# Esp01Shunt.net
KiCad netlist of a schematic drawn in EAGLE
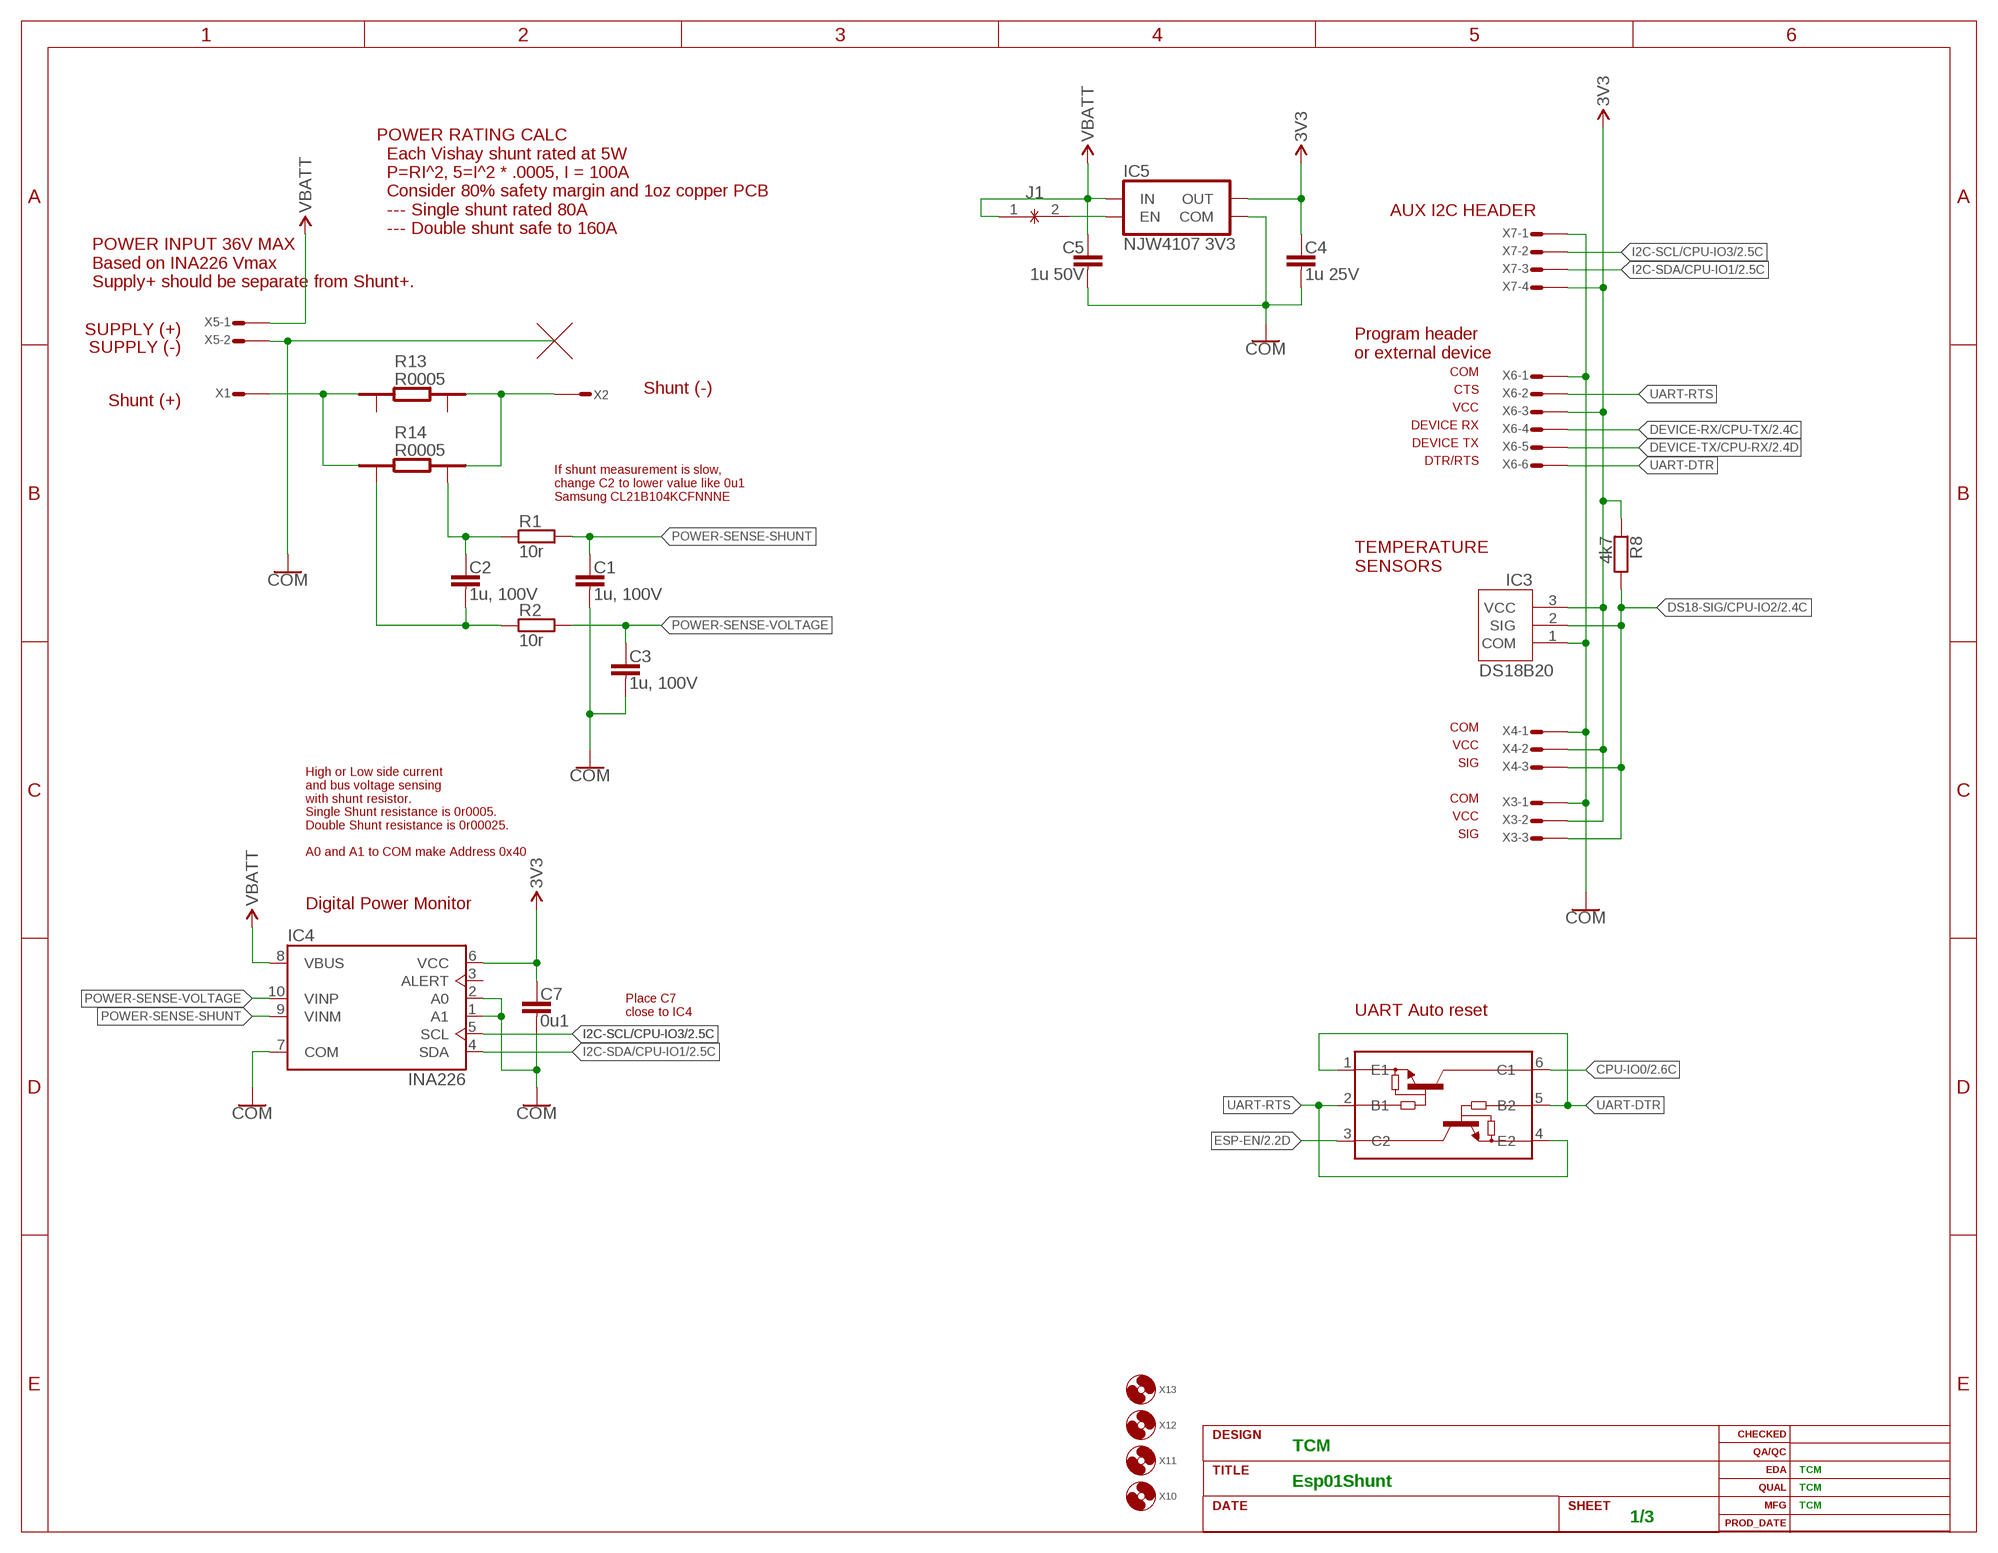
[diagram p0: schematic, sheet 1]
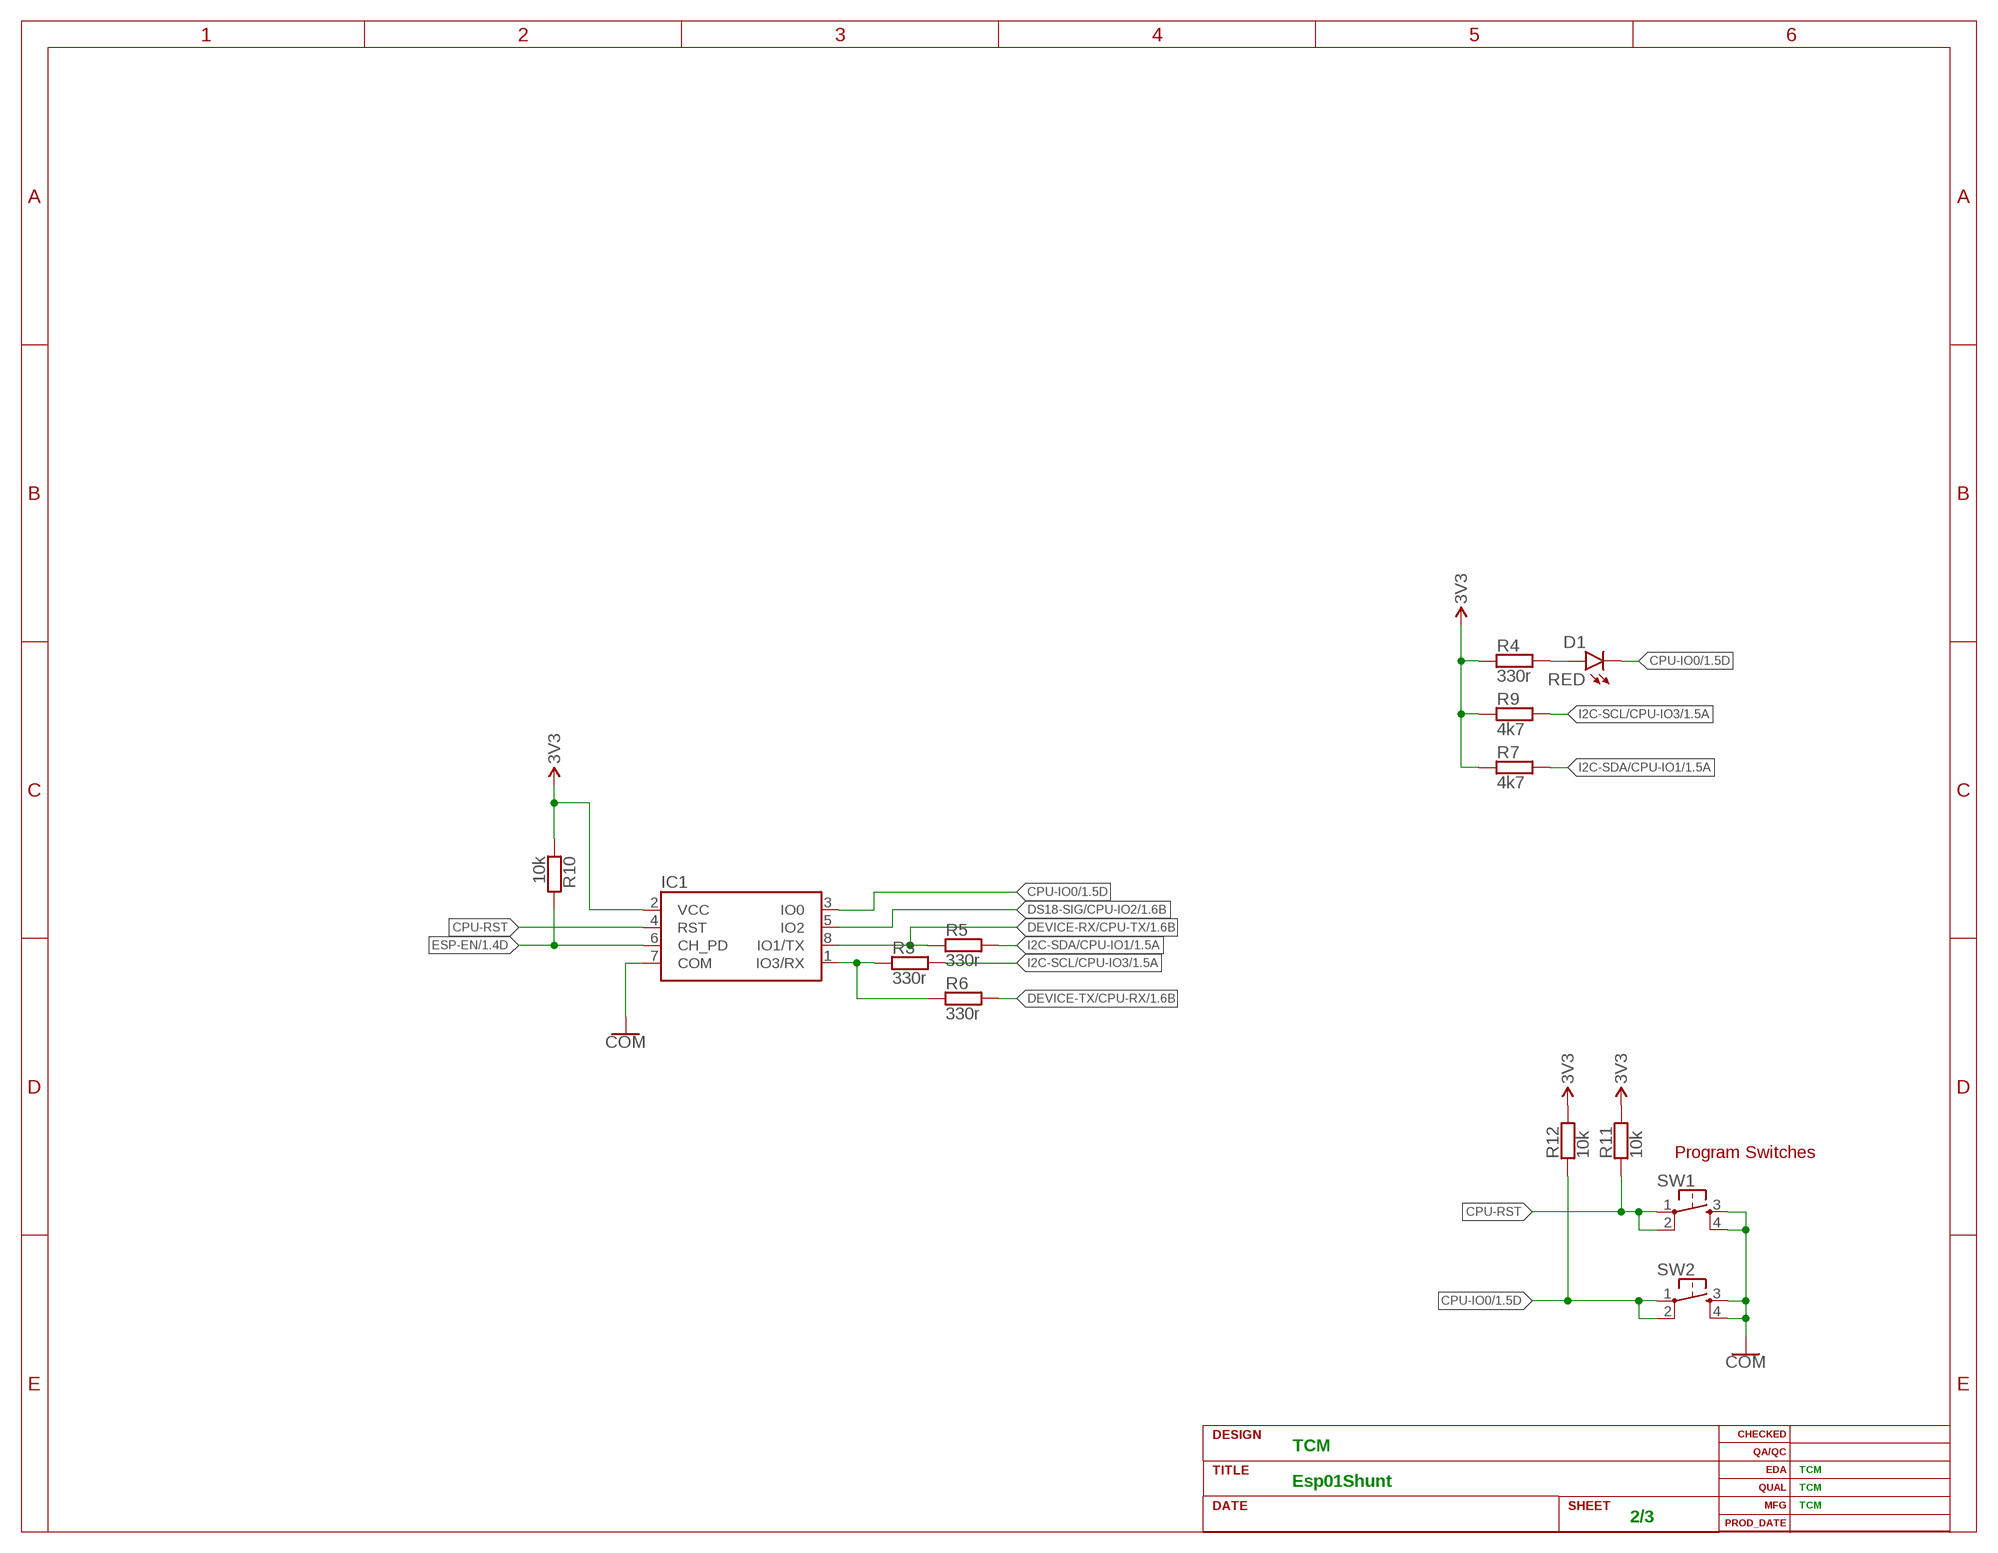
[diagram p1: schematic, sheet 2]
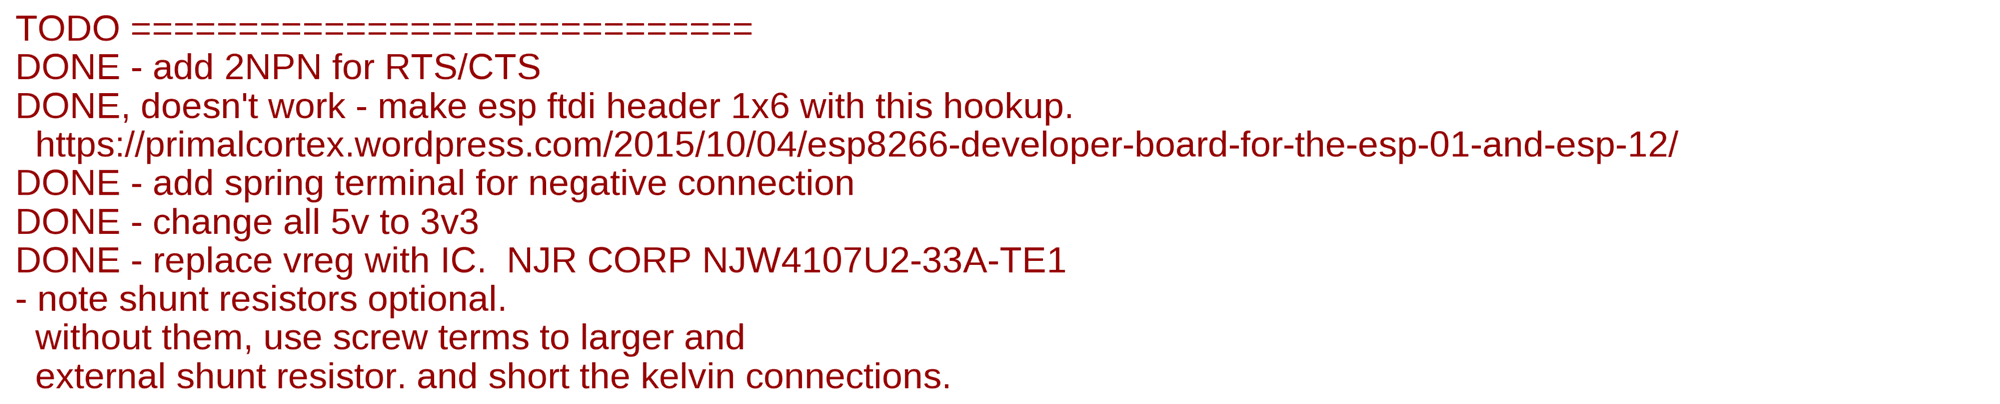
[diagram p2: schematic, sheet 3]

(export (version "E")
  (design (tool "Eeschema 10.0.6"))
  (components
    (comp (ref "D1")
      (value "RED")
      (footprint "eagle-import:LED-0805")
      (fields (field (name "MFG") "OSRAM"))
      (libsource (lib "eagle-import") (part "LED-0805-RED"))
    )
    (comp (ref "IC1")
      (value "ESP8266-01")
      (footprint "eagle-import:ESP8266-01")
      (fields (field (name "MFG") "ESPRESSIF"))
      (libsource (lib "eagle-import") (part "ESP8266-01"))
    )
    (comp (ref "R3")
      (value "330r")
      (footprint "eagle-import:R0603")
      (fields (field (name "MFG_PN") "ERJ-3EKF3300V"))
      (libsource (lib "eagle-import") (part "R-0603"))
    )
    (comp (ref "R4")
      (value "330r")
      (footprint "eagle-import:R0603")
      (fields (field (name "MFG_PN") "ERJ-3EKF3300V"))
      (libsource (lib "eagle-import") (part "R-0603"))
    )
    (comp (ref "R5")
      (value "330r")
      (footprint "eagle-import:R0603")
      (fields (field (name "MFG_PN") "ERJ-3EKF3300V"))
      (libsource (lib "eagle-import") (part "R-0603"))
    )
    (comp (ref "R6")
      (value "330r")
      (footprint "eagle-import:R0603")
      (fields (field (name "MFG_PN") "ERJ-3EKF3300V"))
      (libsource (lib "eagle-import") (part "R-0603"))
    )
    (comp (ref "R7")
      (value "4k7")
      (footprint "eagle-import:R0603")
      (fields (field (name "MFG_PN") "ERJ-3GEYJ472V"))
      (libsource (lib "eagle-import") (part "R-0603"))
    )
    (comp (ref "R9")
      (value "4k7")
      (footprint "eagle-import:R0603")
      (fields (field (name "MFG_PN") "ERJ-3GEYJ472V"))
      (libsource (lib "eagle-import") (part "R-0603"))
    )
    (comp (ref "R10")
      (value "10k")
      (footprint "eagle-import:R0603")
      (fields (field (name "MFG_PN") "ERJ-3GEYJ103V"))
      (libsource (lib "eagle-import") (part "R-0603"))
    )
    (comp (ref "R11")
      (value "10k")
      (footprint "eagle-import:R0603")
      (fields (field (name "MFG_PN") "ERJ-3GEYJ103V"))
      (libsource (lib "eagle-import") (part "R-0603"))
    )
    (comp (ref "R12")
      (value "10k")
      (footprint "eagle-import:R0603")
      (fields (field (name "MFG_PN") "ERJ-3GEYJ103V"))
      (libsource (lib "eagle-import") (part "R-0603"))
    )
    (comp (ref "SW1")
      (value "SWITCH-TACTILE-DOUBLE-SMD")
      (footprint "eagle-import:SWITCH-TACTILE-6MM-SMD")
      (fields (field (name "MFG") "C&K"))
      (libsource (lib "eagle-import") (part "SWITCH-TACTILE-DOUBLE-SMD"))
    )
    (comp (ref "SW2")
      (value "SWITCH-TACTILE-DOUBLE-SMD")
      (footprint "eagle-import:SWITCH-TACTILE-6MM-SMD")
      (fields (field (name "MFG") "C&K"))
      (libsource (lib "eagle-import") (part "SWITCH-TACTILE-DOUBLE-SMD"))
    )
    (comp (ref "C1")
      (value "1u, 100V")
      (footprint "eagle-import:1206")
      (fields (field (name "MFG") "SAMSUNG") (field (name "MFG_PN") "CL31B105KCHNNNE"))
      (libsource (lib "eagle-import") (part "C-1206"))
    )
    (comp (ref "C2")
      (value "1u, 100V")
      (footprint "eagle-import:1206")
      (fields (field (name "MFG") "SAMSUNG") (field (name "MFG_PN") "CL31B105KCHNNNE"))
      (libsource (lib "eagle-import") (part "C-1206"))
    )
    (comp (ref "C3")
      (value "1u, 100V")
      (footprint "eagle-import:1206")
      (fields (field (name "MFG") "SAMSUNG") (field (name "MFG_PN") "CL31B105KCHNNNE"))
      (libsource (lib "eagle-import") (part "C-1206"))
    )
    (comp (ref "C4")
      (value "1u 25V")
      (footprint "eagle-import:C0603")
      (fields (field (name "MFG_PN") "C1608X7R1E105K080AE"))
      (libsource (lib "eagle-import") (part "C-0603"))
    )
    (comp (ref "C5")
      (value "1u 50V")
      (footprint "eagle-import:C0603")
      (fields (field (name "MFG_PN") "C1608X5R1H105K080AB"))
      (libsource (lib "eagle-import") (part "C-0603"))
    )
    (comp (ref "C7")
      (value "0u1")
      (footprint "eagle-import:C0603")
      (fields (field (name "MFG_PN") "VJ0603Y104JXXAC"))
      (libsource (lib "eagle-import") (part "C-0603"))
    )
    (comp (ref "IC2")
      (value "MUN5214DW1T1G")
      (footprint "eagle-import:TSSOP6")
      (fields (field (name "MFG") "ONSEMI") (field (name "MFG_PN") "MUN5214DW1T1G"))
      (libsource (lib "eagle-import") (part "MUN5214-TSSOP6DW1T1G"))
    )
    (comp (ref "IC3")
      (value "DS18B20")
      (footprint "eagle-import:TO92-INLINE")
      (libsource (lib "eagle-import") (part "DS18B20-TO92-INLINE"))
    )
    (comp (ref "IC4")
      (value "INA226")
      (footprint "eagle-import:VSSOP10")
      (fields (field (name "MFG") "TEXAS"))
      (libsource (lib "eagle-import") (part "INA226-VSSOP10"))
    )
    (comp (ref "IC5")
      (value "NJW4107 3V3")
      (footprint "eagle-import:SOT89-5")
      (fields (field (name "MFG") "NJR CORP"))
      (libsource (lib "eagle-import") (part "VREG-WITH-EN-NJW4107-SOT89-5-3V3"))
    )
    (comp (ref "J1")
      (value "JUMPER-60X20-NC")
      (footprint "eagle-import:JUMPER-60X20")
      (libsource (lib "eagle-import") (part "JUMPER-60X20-NC"))
    )
    (comp (ref "R1")
      (value "10r")
      (footprint "eagle-import:R0805")
      (libsource (lib "eagle-import") (part "R-0805"))
    )
    (comp (ref "R2")
      (value "10r")
      (footprint "eagle-import:R0805")
      (libsource (lib "eagle-import") (part "R-0805"))
    )
    (comp (ref "R8")
      (value "4k7")
      (footprint "eagle-import:R0603")
      (fields (field (name "MFG_PN") "ERJ-3GEYJ472V"))
      (libsource (lib "eagle-import") (part "R-0603"))
    )
    (comp (ref "R13")
      (value "R0005")
      (footprint "eagle-import:RES-SHUNT-WSK1216")
      (fields (field (name "MFG") "VISHAY"))
      (libsource (lib "eagle-import") (part "R-SHUNT-4TERM-WSK1216-R0005"))
    )
    (comp (ref "R14")
      (value "R0005")
      (footprint "eagle-import:RES-SHUNT-WSK1216")
      (fields (field (name "MFG") "VISHAY"))
      (libsource (lib "eagle-import") (part "R-SHUNT-4TERM-WSK1216-R0005"))
    )
    (comp (ref "X1")
      (value "CON-SCREW-V-30AMP")
      (footprint "eagle-import:CON-SCREW-V-30AMP")
      (fields (field (name "MFG") "KEYSTONE"))
      (libsource (lib "eagle-import") (part "CON-SCREW-V-30AMP"))
    )
    (comp (ref "X2")
      (value "CON-SCREW-V-30AMP")
      (footprint "eagle-import:CON-SCREW-V-30AMP")
      (fields (field (name "MFG") "KEYSTONE"))
      (libsource (lib "eagle-import") (part "CON-SCREW-V-30AMP"))
    )
    (comp (ref "X3")
      (value "CON-1X3")
      (footprint "eagle-import:CON-1X3")
      (libsource (lib "eagle-import") (part "CON-1X3"))
    )
    (comp (ref "X4")
      (value "CON-1X3")
      (footprint "eagle-import:CON-1X3")
      (libsource (lib "eagle-import") (part "CON-1X3"))
    )
    (comp (ref "X5")
      (value "CON-1X2-TERM-SPRING-5MM-2834082-1")
      (footprint "eagle-import:CON-1X2-TERM-SPRING-5MM-2834082-1")
      (fields (field (name "MFG") "TE CONN"))
      (libsource (lib "eagle-import") (part "CON-1X2-TERM-SPRING-5MM-2834082-1"))
    )
    (comp (ref "X6")
      (value "CON-1X6-UART-DCE")
      (footprint "eagle-import:CON-1X6-UART-DCE")
      (libsource (lib "eagle-import") (part "CON-1X6-UART-DCE"))
    )
    (comp (ref "X7")
      (value "CON-1X4")
      (footprint "eagle-import:CON-1X4")
      (libsource (lib "eagle-import") (part "CON-1X4"))
    )
    (comp (ref "X10")
      (value "HOLE-NO-PAD-NO-SILK")
      (footprint "eagle-import:M3-NO-PAD-NO-SILK")
      (libsource (lib "eagle-import") (part "HOLE-NO-PAD-NO-SILK"))
    )
    (comp (ref "X11")
      (value "HOLE-NO-PAD-NO-SILK")
      (footprint "eagle-import:M3-NO-PAD-NO-SILK")
      (libsource (lib "eagle-import") (part "HOLE-NO-PAD-NO-SILK"))
    )
    (comp (ref "X12")
      (value "HOLE-NO-PAD-NO-SILK")
      (footprint "eagle-import:M3-NO-PAD-NO-SILK")
      (libsource (lib "eagle-import") (part "HOLE-NO-PAD-NO-SILK"))
    )
    (comp (ref "X13")
      (value "HOLE-NO-PAD-NO-SILK")
      (footprint "eagle-import:M3-NO-PAD-NO-SILK")
      (libsource (lib "eagle-import") (part "HOLE-NO-PAD-NO-SILK"))
    )
  )
  (nets
    (net (code "1") (name "3V3") (class "Default")
      (node (ref "C4") (pin "1") (pinfunction "1_1") (pintype "passive"))
      (node (ref "C7") (pin "1") (pinfunction "1_1") (pintype "passive"))
      (node (ref "IC1") (pin "2") (pinfunction "VCC_2") (pintype "power_in"))
      (node (ref "IC3") (pin "3") (pinfunction "VCC_3") (pintype "power_in"))
      (node (ref "IC4") (pin "6") (pinfunction "VCC_6") (pintype "power_in"))
      (node (ref "IC5") (pin "4") (pinfunction "OUT_4") (pintype "power_in"))
      (node (ref "R10") (pin "1") (pinfunction "1_1") (pintype "passive"))
      (node (ref "R11") (pin "2") (pinfunction "2_2") (pintype "passive"))
      (node (ref "R12") (pin "2") (pinfunction "2_2") (pintype "passive"))
      (node (ref "R4") (pin "1") (pinfunction "1_1") (pintype "passive"))
      (node (ref "R7") (pin "1") (pinfunction "1_1") (pintype "passive"))
      (node (ref "R8") (pin "1") (pinfunction "1_1") (pintype "passive"))
      (node (ref "R9") (pin "1") (pinfunction "1_1") (pintype "passive"))
      (node (ref "X3") (pin "2") (pinfunction "S_2") (pintype "passive"))
      (node (ref "X4") (pin "2") (pinfunction "S_2") (pintype "passive"))
      (node (ref "X6") (pin "3") (pinfunction "S_3") (pintype "passive"))
      (node (ref "X7") (pin "4") (pinfunction "S_4") (pintype "passive"))
    )
    (net (code "2") (name "COM") (class "Default")
      (node (ref "C1") (pin "2") (pinfunction "2_2") (pintype "passive"))
      (node (ref "C3") (pin "2") (pinfunction "2_2") (pintype "passive"))
      (node (ref "C4") (pin "2") (pinfunction "2_2") (pintype "passive"))
      (node (ref "C5") (pin "2") (pinfunction "2_2") (pintype "passive"))
      (node (ref "C7") (pin "2") (pinfunction "2_2") (pintype "passive"))
      (node (ref "IC1") (pin "7") (pinfunction "COM_7") (pintype "power_in"))
      (node (ref "IC3") (pin "1") (pinfunction "COM_1") (pintype "power_in"))
      (node (ref "IC4") (pin "1") (pinfunction "A1_1") (pintype "input"))
      (node (ref "IC4") (pin "2") (pinfunction "A0_2") (pintype "input"))
      (node (ref "IC4") (pin "7") (pinfunction "COM_7") (pintype "power_in"))
      (node (ref "IC5") (pin "2") (pinfunction "COM_2") (pintype "power_in"))
      (node (ref "IC5") (pin "5") (pinfunction "COM_5") (pintype "power_in"))
      (node (ref "SW1") (pin "3") (pinfunction "3_3") (pintype "passive"))
      (node (ref "SW1") (pin "4") (pinfunction "4_4") (pintype "passive"))
      (node (ref "SW2") (pin "3") (pinfunction "3_3") (pintype "passive"))
      (node (ref "SW2") (pin "4") (pinfunction "4_4") (pintype "passive"))
      (node (ref "X3") (pin "1") (pinfunction "S_1") (pintype "passive"))
      (node (ref "X4") (pin "1") (pinfunction "S_1") (pintype "passive"))
      (node (ref "X5") (pin "3") (pinfunction "S_3") (pintype "passive"))
      (node (ref "X5") (pin "4") (pinfunction "S_4") (pintype "passive"))
      (node (ref "X6") (pin "1") (pinfunction "S_1") (pintype "passive"))
      (node (ref "X7") (pin "1") (pinfunction "S_1") (pintype "passive"))
    )
    (net (code "3") (name "CPU-IO0") (class "Default")
      (node (ref "D1") (pin "-") (pinfunction "C_-") (pintype "passive"))
      (node (ref "IC1") (pin "3") (pinfunction "IO0_3") (pintype "bidirectional"))
      (node (ref "IC2") (pin "6") (pinfunction "C1_6") (pintype "bidirectional"))
      (node (ref "R12") (pin "1") (pinfunction "1_1") (pintype "passive"))
      (node (ref "SW2") (pin "1") (pinfunction "1_1") (pintype "passive"))
      (node (ref "SW2") (pin "2") (pinfunction "2_2") (pintype "passive"))
    )
    (net (code "4") (name "CPU-RST") (class "Default")
      (node (ref "IC1") (pin "4") (pinfunction "RST_4") (pintype "input"))
      (node (ref "R11") (pin "1") (pinfunction "1_1") (pintype "passive"))
      (node (ref "SW1") (pin "1") (pinfunction "1_1") (pintype "passive"))
      (node (ref "SW1") (pin "2") (pinfunction "2_2") (pintype "passive"))
    )
    (net (code "5") (name "DEVICE-RX{slash}CPU-TX") (class "Default")
      (node (ref "IC1") (pin "8") (pinfunction "IO1/TX_8") (pintype "output"))
      (node (ref "R5") (pin "1") (pinfunction "1_1") (pintype "passive"))
      (node (ref "X6") (pin "4") (pinfunction "S_4") (pintype "passive"))
    )
    (net (code "6") (name "DEVICE-TX{slash}CPU-RX") (class "Default")
      (node (ref "R6") (pin "2") (pinfunction "2_2") (pintype "passive"))
      (node (ref "X6") (pin "5") (pinfunction "S_5") (pintype "passive"))
    )
    (net (code "7") (name "DS18-SIG{slash}CPU-IO2") (class "Default")
      (node (ref "IC1") (pin "5") (pinfunction "IO2_5") (pintype "bidirectional"))
      (node (ref "IC3") (pin "2") (pinfunction "SIG_2") (pintype "bidirectional"))
      (node (ref "R8") (pin "2") (pinfunction "2_2") (pintype "passive"))
      (node (ref "X3") (pin "3") (pinfunction "S_3") (pintype "passive"))
      (node (ref "X4") (pin "3") (pinfunction "S_3") (pintype "passive"))
    )
    (net (code "8") (name "ESP-EN") (class "Default")
      (node (ref "IC1") (pin "6") (pinfunction "CH_PD_6") (pintype "bidirectional"))
      (node (ref "IC2") (pin "3") (pinfunction "C2_3") (pintype "bidirectional"))
      (node (ref "R10") (pin "2") (pinfunction "2_2") (pintype "passive"))
    )
    (net (code "9") (name "I2C-SCL{slash}CPU-IO3") (class "Default")
      (node (ref "IC4") (pin "5") (pinfunction "SCL_5") (pintype "input"))
      (node (ref "R3") (pin "2") (pinfunction "2_2") (pintype "passive"))
      (node (ref "R9") (pin "2") (pinfunction "2_2") (pintype "passive"))
      (node (ref "X7") (pin "2") (pinfunction "S_2") (pintype "passive"))
    )
    (net (code "10") (name "I2C-SDA{slash}CPU-IO1") (class "Default")
      (node (ref "IC4") (pin "4") (pinfunction "SDA_4") (pintype "bidirectional"))
      (node (ref "R5") (pin "2") (pinfunction "2_2") (pintype "passive"))
      (node (ref "R7") (pin "2") (pinfunction "2_2") (pintype "passive"))
      (node (ref "X7") (pin "3") (pinfunction "S_3") (pintype "passive"))
    )
    (net (code "11") (name "Net-(D1-A)") (class "Default")
      (node (ref "D1") (pin "+") (pinfunction "A_+") (pintype "passive"))
      (node (ref "R4") (pin "2") (pinfunction "2_2") (pintype "passive"))
    )
    (net (code "12") (name "Net-(IC1-IO3{slash}RX)") (class "Default")
      (node (ref "IC1") (pin "1") (pinfunction "IO3/RX_1") (pintype "input"))
      (node (ref "R3") (pin "1") (pinfunction "1_1") (pintype "passive"))
      (node (ref "R6") (pin "1") (pinfunction "1_1") (pintype "passive"))
    )
    (net (code "13") (name "Net-(IC5-EN)") (class "Default")
      (node (ref "IC5") (pin "1") (pinfunction "EN_1") (pintype "power_in"))
      (node (ref "J1") (pin "2") (pinfunction "P$2_2") (pintype "bidirectional"))
    )
    (net (code "14") (name "Net-(R1-1)") (class "Default")
      (node (ref "C2") (pin "1") (pinfunction "1_1") (pintype "passive"))
      (node (ref "R1") (pin "+") (pinfunction "1_+") (pintype "passive"))
      (node (ref "R14") (pin "3") (pinfunction "3_3") (pintype "passive"))
    )
    (net (code "15") (name "Net-(R2-1)") (class "Default")
      (node (ref "C2") (pin "2") (pinfunction "2_2") (pintype "passive"))
      (node (ref "R14") (pin "2") (pinfunction "2_2") (pintype "passive"))
      (node (ref "R2") (pin "+") (pinfunction "1_+") (pintype "passive"))
    )
    (net (code "16") (name "Net-(R13-Pad1)") (class "Default")
      (node (ref "R13") (pin "1") (pinfunction "1_1") (pintype "passive"))
      (node (ref "R14") (pin "1") (pinfunction "1_1") (pintype "passive"))
      (node (ref "X1") (pin "1") (pinfunction "S_1") (pintype "passive"))
      (node (ref "X1") (pin "2") (pinfunction "S_2") (pintype "passive"))
      (node (ref "X1") (pin "3") (pinfunction "S_3") (pintype "passive"))
      (node (ref "X1") (pin "4") (pinfunction "S_4") (pintype "passive"))
      (node (ref "X1") (pin "5") (pinfunction "S_5") (pintype "passive"))
      (node (ref "X1") (pin "6") (pinfunction "S_6") (pintype "passive"))
    )
    (net (code "17") (name "Net-(R13-Pad4)") (class "Default")
      (node (ref "R13") (pin "4") (pinfunction "4_4") (pintype "passive"))
      (node (ref "R14") (pin "4") (pinfunction "4_4") (pintype "passive"))
      (node (ref "X2") (pin "1") (pinfunction "S_1") (pintype "passive"))
      (node (ref "X2") (pin "2") (pinfunction "S_2") (pintype "passive"))
      (node (ref "X2") (pin "3") (pinfunction "S_3") (pintype "passive"))
      (node (ref "X2") (pin "4") (pinfunction "S_4") (pintype "passive"))
      (node (ref "X2") (pin "5") (pinfunction "S_5") (pintype "passive"))
      (node (ref "X2") (pin "6") (pinfunction "S_6") (pintype "passive"))
    )
    (net (code "18") (name "POWER-SENSE-SHUNT") (class "Default")
      (node (ref "C1") (pin "1") (pinfunction "1_1") (pintype "passive"))
      (node (ref "IC4") (pin "9") (pinfunction "VINM_9") (pintype "input"))
      (node (ref "R1") (pin "-") (pinfunction "2_-") (pintype "passive"))
    )
    (net (code "19") (name "POWER-SENSE-VOLTAGE") (class "Default")
      (node (ref "C3") (pin "1") (pinfunction "1_1") (pintype "passive"))
      (node (ref "IC4") (pin "10") (pinfunction "VINP_10") (pintype "input"))
      (node (ref "R2") (pin "-") (pinfunction "2_-") (pintype "passive"))
    )
    (net (code "20") (name "UART-DTR") (class "Default")
      (node (ref "IC2") (pin "1") (pinfunction "E1_1") (pintype "bidirectional"))
      (node (ref "IC2") (pin "5") (pinfunction "B2_5") (pintype "bidirectional"))
      (node (ref "X6") (pin "6") (pinfunction "S_6") (pintype "passive"))
    )
    (net (code "21") (name "UART-RTS") (class "Default")
      (node (ref "IC2") (pin "2") (pinfunction "B1_2") (pintype "bidirectional"))
      (node (ref "IC2") (pin "4") (pinfunction "E2_4") (pintype "bidirectional"))
      (node (ref "X6") (pin "2") (pinfunction "S_2") (pintype "passive"))
    )
    (net (code "22") (name "VBATT") (class "Default")
      (node (ref "C5") (pin "1") (pinfunction "1_1") (pintype "passive"))
      (node (ref "IC4") (pin "8") (pinfunction "VBUS_8") (pintype "input"))
      (node (ref "IC5") (pin "6") (pinfunction "IN_6") (pintype "power_in"))
      (node (ref "J1") (pin "1") (pinfunction "P$1_1") (pintype "bidirectional"))
      (node (ref "X5") (pin "1") (pinfunction "S_1") (pintype "passive"))
      (node (ref "X5") (pin "2") (pinfunction "S_2") (pintype "passive"))
    )
    (net (code "23") (name "unconnected-(IC4-ALERT-Pad3)") (class "Default")
      (node (ref "IC4") (pin "3") (pinfunction "ALERT_3") (pintype "input"))
    )
    (net (code "24") (name "unconnected-(R13-Pad2)") (class "Default")
      (node (ref "R13") (pin "2") (pinfunction "2_2") (pintype "passive"))
    )
    (net (code "25") (name "unconnected-(R13-Pad3)") (class "Default")
      (node (ref "R13") (pin "3") (pinfunction "3_3") (pintype "passive"))
    )
  )
)
